# MicroSD.net
KiCad netlist of a schematic drawn in Altium Designer
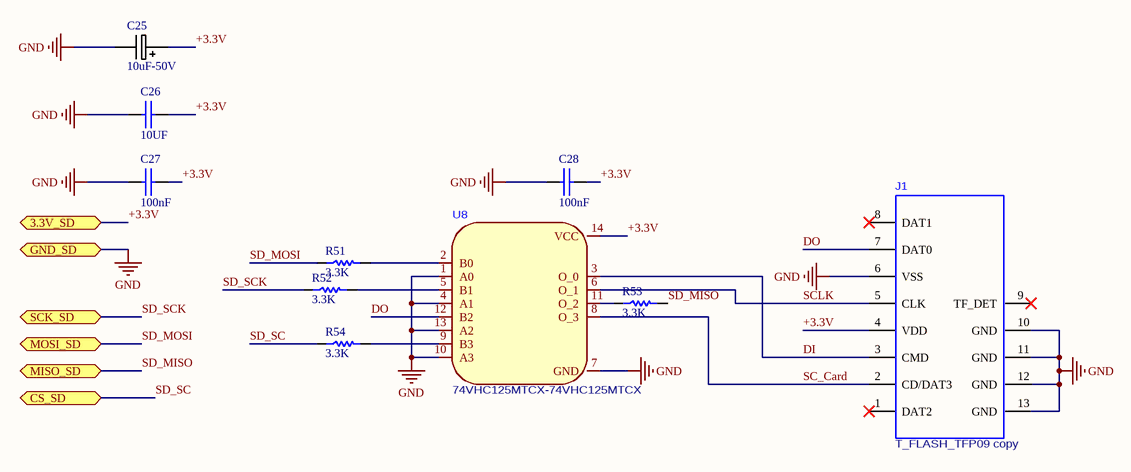
[diagram p0: MicroSD.SchDoc]

(export (version "E")
  (design (tool "Eeschema 10.0.6"))
  (components
    (comp (ref "C25")
      (value "10uF-50V")
      (footprint "PANACAP-D-GENERIC")
      (description "GENERIC CAPACITOR POLARISED")
      (libsource (lib "vh_altium_library") (part "PANACAP-10UF-50V-FK"))
    )
    (comp (ref "C26")
      (value "10UF")
      (footprint "SMD_CAP_0805")
      (description "Bipolar Capacitor")
      (fields (field (name "VOLTAGE") "100V") (field (name "DESIGNER") "Saeid Jorablo"))
      (libsource (lib "Electrovolt Lib") (part "Cap-Bipolar"))
    )
    (comp (ref "C27")
      (value "100nF")
      (footprint "SMD_CAP_0805")
      (description "Bipolar Capacitor")
      (fields (field (name "VOLTAGE") "100V") (field (name "DESIGNER") "Saeid Jorablo"))
      (libsource (lib "Electrovolt Lib") (part "Cap-Bipolar"))
    )
    (comp (ref "C28")
      (value "100nF")
      (footprint "SMD_CAP_0805")
      (description "Bipolar Capacitor")
      (fields (field (name "VOLTAGE") "100V") (field (name "DESIGNER") "Saeid Jorablo"))
      (libsource (lib "Electrovolt Lib") (part "Cap-Bipolar"))
    )
    (comp (ref "J1")
      (value "T_FLASH_TFP09 copy")
      (footprint "TFP09-2-12B-MOD")
      (libsource (lib "Schlib_1") (part "T_FLASH_TFP09 copy"))
    )
    (comp (ref "R51")
      (value "3.3K")
      (footprint "RES 0805 (2012X06L)")
      (description "Resistor")
      (fields (field (name "TOLERANCE") "5%") (field (name "POWER") "1/8 W"))
      (libsource (lib "Electrovolt Lib") (part "Resistor"))
    )
    (comp (ref "R52")
      (value "3.3K")
      (footprint "RES 0805 (2012X06L)")
      (description "Resistor")
      (fields (field (name "TOLERANCE") "5%") (field (name "POWER") "1/8 W"))
      (libsource (lib "Electrovolt Lib") (part "Resistor"))
    )
    (comp (ref "R53")
      (value "3.3K")
      (footprint "RES 0805 (2012X06L)")
      (description "Resistor")
      (fields (field (name "TOLERANCE") "5%") (field (name "POWER") "1/8 W"))
      (libsource (lib "Electrovolt Lib") (part "Resistor"))
    )
    (comp (ref "R54")
      (value "3.3K")
      (footprint "RES 0805 (2012X06L)")
      (description "Resistor")
      (fields (field (name "TOLERANCE") "5%") (field (name "POWER") "1/8 W"))
      (libsource (lib "Electrovolt Lib") (part "Resistor"))
    )
    (comp (ref "U8")
      (value "74VHC125MTCX-74VHC125MTCX")
      (footprint "SOP65P640X120-14N")
      (libsource (lib "Schlib_1") (part "74VHC125MTCX-74VHC125MTCX"))
    )
  )
  (nets
    (net (code "1") (name "/+3.3V") (class "Default")
      (node (ref "C25") (pin "+") (pinfunction "+_+") (pintype "passive"))
      (node (ref "C26") (pin "2") (pinfunction "-_2") (pintype "passive"))
      (node (ref "C27") (pin "2") (pinfunction "-_2") (pintype "passive"))
      (node (ref "C28") (pin "2") (pinfunction "-_2") (pintype "passive"))
      (node (ref "J1") (pin "4") (pinfunction "VDD_4") (pintype "passive"))
      (node (ref "U8") (pin "14") (pinfunction "VCC_14") (pintype "passive"))
    )
    (net (code "2") (name "/DI") (class "Default")
      (node (ref "J1") (pin "3") (pinfunction "CMD_3") (pintype "passive"))
      (node (ref "U8") (pin "3") (pinfunction "O_0_3") (pintype "passive"))
    )
    (net (code "3") (name "/DO") (class "Default")
      (node (ref "J1") (pin "7") (pinfunction "DAT0_7") (pintype "passive"))
      (node (ref "U8") (pin "12") (pinfunction "B2_12") (pintype "passive"))
    )
    (net (code "4") (name "/SCLK") (class "Default")
      (node (ref "J1") (pin "5") (pinfunction "CLK_5") (pintype "passive"))
      (node (ref "U8") (pin "6") (pinfunction "O_1_6") (pintype "passive"))
    )
    (net (code "5") (name "/SC_Card") (class "Default")
      (node (ref "J1") (pin "2") (pinfunction "CD/DAT3_2") (pintype "passive"))
      (node (ref "U8") (pin "8") (pinfunction "O_3_8") (pintype "passive"))
    )
    (net (code "6") (name "/SD_MISO") (class "Default")
      (node (ref "R53") (pin "2") (pinfunction "2_2") (pintype "passive"))
    )
    (net (code "7") (name "/SD_MOSI") (class "Default")
      (node (ref "R51") (pin "1") (pinfunction "1_1") (pintype "passive"))
    )
    (net (code "8") (name "/SD_SC") (class "Default")
      (node (ref "R54") (pin "1") (pinfunction "1_1") (pintype "passive"))
    )
    (net (code "9") (name "/SD_SCK") (class "Default")
      (node (ref "R52") (pin "1") (pinfunction "1_1") (pintype "passive"))
    )
    (net (code "10") (name "GND") (class "Default")
      (node (ref "C25") (pin "-") (pinfunction "-_-") (pintype "passive"))
      (node (ref "C26") (pin "1") (pinfunction "+_1") (pintype "passive"))
      (node (ref "C27") (pin "1") (pinfunction "+_1") (pintype "passive"))
      (node (ref "C28") (pin "1") (pinfunction "+_1") (pintype "passive"))
      (node (ref "J1") (pin "10") (pinfunction "GND_10") (pintype "passive"))
      (node (ref "J1") (pin "11") (pinfunction "GND_11") (pintype "passive"))
      (node (ref "J1") (pin "12") (pinfunction "GND_12") (pintype "passive"))
      (node (ref "J1") (pin "13") (pinfunction "GND_13") (pintype "passive"))
      (node (ref "J1") (pin "6") (pinfunction "VSS_6") (pintype "passive"))
      (node (ref "U8") (pin "1") (pinfunction "A0_1") (pintype "passive"))
      (node (ref "U8") (pin "10") (pinfunction "A3_10") (pintype "passive"))
      (node (ref "U8") (pin "13") (pinfunction "A2_13") (pintype "passive"))
      (node (ref "U8") (pin "4") (pinfunction "A1_4") (pintype "passive"))
      (node (ref "U8") (pin "7") (pinfunction "GND_7") (pintype "passive"))
    )
    (net (code "11") (name "Net-(U8-B0)") (class "Default")
      (node (ref "R51") (pin "2") (pinfunction "2_2") (pintype "passive"))
      (node (ref "U8") (pin "2") (pinfunction "B0_2") (pintype "passive"))
    )
    (net (code "12") (name "Net-(U8-B1)") (class "Default")
      (node (ref "R52") (pin "2") (pinfunction "2_2") (pintype "passive"))
      (node (ref "U8") (pin "5") (pinfunction "B1_5") (pintype "passive"))
    )
    (net (code "13") (name "Net-(U8-B3)") (class "Default")
      (node (ref "R54") (pin "2") (pinfunction "2_2") (pintype "passive"))
      (node (ref "U8") (pin "9") (pinfunction "B3_9") (pintype "passive"))
    )
    (net (code "14") (name "Net-(U8-O_2)") (class "Default")
      (node (ref "R53") (pin "1") (pinfunction "1_1") (pintype "passive"))
      (node (ref "U8") (pin "11") (pinfunction "O_2_11") (pintype "passive"))
    )
    (net (code "15") (name "unconnected-(J1-DAT1-Pad8)") (class "Default")
      (node (ref "J1") (pin "8") (pinfunction "DAT1_8") (pintype "passive+no_connect"))
    )
    (net (code "16") (name "unconnected-(J1-DAT2-Pad1)") (class "Default")
      (node (ref "J1") (pin "1") (pinfunction "DAT2_1") (pintype "passive+no_connect"))
    )
    (net (code "17") (name "unconnected-(J1-TF_DET-Pad9)") (class "Default")
      (node (ref "J1") (pin "9") (pinfunction "TF_DET_9") (pintype "passive+no_connect"))
    )
  )
)
